# preamp.net
KiCad netlist of a schematic drawn in EAGLE
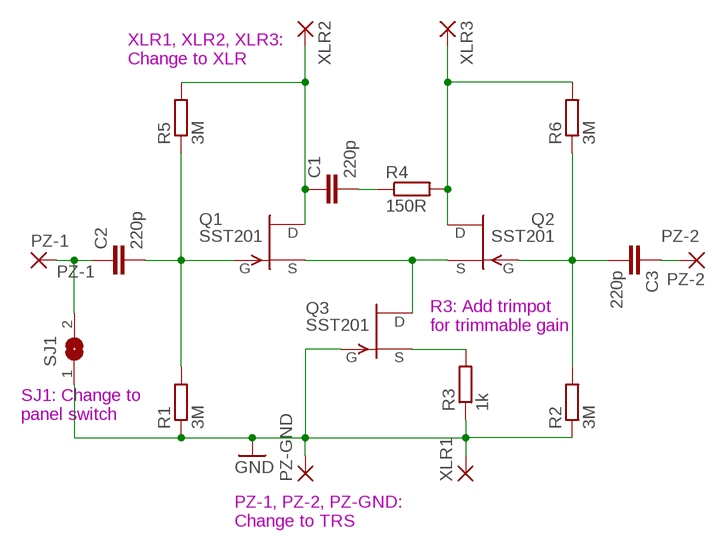
[diagram p0: schematic, sheet 1]

(export (version "E")
  (design (tool "Eeschema 10.0.6"))
  (components
    (comp (ref "C1")
      (value "220p")
      (footprint "eagle-import:C1206")
      (libsource (lib "eagle-import") (part "C-EUC1206"))
    )
    (comp (ref "C2")
      (value "220p")
      (footprint "eagle-import:C1206")
      (libsource (lib "eagle-import") (part "C-EUC1206"))
    )
    (comp (ref "C3")
      (value "220p")
      (footprint "eagle-import:C1206")
      (libsource (lib "eagle-import") (part "C-EUC1206"))
    )
    (comp (ref "PZ-1")
      (value "3,17/1,3")
      (footprint "eagle-import:3,17_1,3")
      (libsource (lib "eagle-import") (part "3,17/1,3"))
    )
    (comp (ref "PZ-2")
      (value "3,17/1,3")
      (footprint "eagle-import:3,17_1,3")
      (libsource (lib "eagle-import") (part "3,17/1,3"))
    )
    (comp (ref "PZ-GND")
      (value "3,17/1,3")
      (footprint "eagle-import:3,17_1,3")
      (libsource (lib "eagle-import") (part "3,17/1,3"))
    )
    (comp (ref "Q1")
      (value "SST201")
      (footprint "eagle-import:SOT23")
      (libsource (lib "eagle-import") (part "?20SST1"))
    )
    (comp (ref "Q2")
      (value "SST201")
      (footprint "eagle-import:SOT23")
      (libsource (lib "eagle-import") (part "?20SST1"))
    )
    (comp (ref "Q3")
      (value "SST201")
      (footprint "eagle-import:SOT23")
      (libsource (lib "eagle-import") (part "?20SST1"))
    )
    (comp (ref "R1")
      (value "3M")
      (footprint "eagle-import:R1206")
      (libsource (lib "eagle-import") (part "R-EU_R1206"))
    )
    (comp (ref "R2")
      (value "3M")
      (footprint "eagle-import:R1206")
      (libsource (lib "eagle-import") (part "R-EU_R1206"))
    )
    (comp (ref "R3")
      (value "1k")
      (footprint "eagle-import:R1206")
      (libsource (lib "eagle-import") (part "R-EU_R1206"))
    )
    (comp (ref "R4")
      (value "150R")
      (footprint "eagle-import:R1206")
      (libsource (lib "eagle-import") (part "R-EU_R1206"))
    )
    (comp (ref "R5")
      (value "3M")
      (footprint "eagle-import:R1206")
      (libsource (lib "eagle-import") (part "R-EU_R1206"))
    )
    (comp (ref "R6")
      (value "3M")
      (footprint "eagle-import:R1206")
      (libsource (lib "eagle-import") (part "R-EU_R1206"))
    )
    (comp (ref "SJ1") (value "SJ") (footprint "eagle-import:SJ") (libsource (lib "eagle-import") (part "SJ")))
    (comp (ref "XLR1")
      (value "3,17/1,3")
      (footprint "eagle-import:3,17_1,3")
      (libsource (lib "eagle-import") (part "3,17/1,3"))
    )
    (comp (ref "XLR2")
      (value "3,17/1,3")
      (footprint "eagle-import:3,17_1,3")
      (libsource (lib "eagle-import") (part "3,17/1,3"))
    )
    (comp (ref "XLR3")
      (value "3,17/1,3")
      (footprint "eagle-import:3,17_1,3")
      (libsource (lib "eagle-import") (part "3,17/1,3"))
    )
  )
  (nets
    (net (code "1") (name "/PZ-1") (class "Default")
      (node (ref "C2") (pin "1") (pinfunction "1_1") (pintype "passive"))
      (node (ref "PZ-1") (pin "1") (pinfunction "P_1") (pintype "passive"))
      (node (ref "SJ1") (pin "2") (pinfunction "2_2") (pintype "passive"))
    )
    (net (code "2") (name "/PZ-2") (class "Default")
      (node (ref "C3") (pin "1") (pinfunction "1_1") (pintype "passive"))
      (node (ref "PZ-2") (pin "1") (pinfunction "P_1") (pintype "passive"))
    )
    (net (code "3") (name "GND") (class "Default")
      (node (ref "PZ-GND") (pin "1") (pinfunction "P_1") (pintype "passive"))
      (node (ref "Q3") (pin "3") (pinfunction "G_3") (pintype "passive"))
      (node (ref "R1") (pin "1") (pinfunction "1_1") (pintype "passive"))
      (node (ref "R2") (pin "1") (pinfunction "1_1") (pintype "passive"))
      (node (ref "R3") (pin "1") (pinfunction "1_1") (pintype "passive"))
      (node (ref "SJ1") (pin "1") (pinfunction "1_1") (pintype "passive"))
      (node (ref "XLR1") (pin "1") (pinfunction "P_1") (pintype "passive"))
    )
    (net (code "4") (name "Net-(C1-Pad2)") (class "Default")
      (node (ref "C1") (pin "2") (pinfunction "2_2") (pintype "passive"))
      (node (ref "R4") (pin "1") (pinfunction "1_1") (pintype "passive"))
    )
    (net (code "5") (name "Net-(Q1-D)") (class "Default")
      (node (ref "C1") (pin "1") (pinfunction "1_1") (pintype "passive"))
      (node (ref "Q1") (pin "1") (pinfunction "D_1") (pintype "passive"))
      (node (ref "R5") (pin "2") (pinfunction "2_2") (pintype "passive"))
      (node (ref "XLR2") (pin "1") (pinfunction "P_1") (pintype "passive"))
    )
    (net (code "6") (name "Net-(Q1-G)") (class "Default")
      (node (ref "C2") (pin "2") (pinfunction "2_2") (pintype "passive"))
      (node (ref "Q1") (pin "3") (pinfunction "G_3") (pintype "passive"))
      (node (ref "R1") (pin "2") (pinfunction "2_2") (pintype "passive"))
      (node (ref "R5") (pin "1") (pinfunction "1_1") (pintype "passive"))
    )
    (net (code "7") (name "Net-(Q1-S)") (class "Default")
      (node (ref "Q1") (pin "2") (pinfunction "S_2") (pintype "passive"))
      (node (ref "Q2") (pin "2") (pinfunction "S_2") (pintype "passive"))
      (node (ref "Q3") (pin "1") (pinfunction "D_1") (pintype "passive"))
    )
    (net (code "8") (name "Net-(Q2-D)") (class "Default")
      (node (ref "Q2") (pin "1") (pinfunction "D_1") (pintype "passive"))
      (node (ref "R4") (pin "2") (pinfunction "2_2") (pintype "passive"))
      (node (ref "R6") (pin "2") (pinfunction "2_2") (pintype "passive"))
      (node (ref "XLR3") (pin "1") (pinfunction "P_1") (pintype "passive"))
    )
    (net (code "9") (name "Net-(Q2-G)") (class "Default")
      (node (ref "C3") (pin "2") (pinfunction "2_2") (pintype "passive"))
      (node (ref "Q2") (pin "3") (pinfunction "G_3") (pintype "passive"))
      (node (ref "R2") (pin "2") (pinfunction "2_2") (pintype "passive"))
      (node (ref "R6") (pin "1") (pinfunction "1_1") (pintype "passive"))
    )
    (net (code "10") (name "Net-(Q3-S)") (class "Default")
      (node (ref "Q3") (pin "2") (pinfunction "S_2") (pintype "passive"))
      (node (ref "R3") (pin "2") (pinfunction "2_2") (pintype "passive"))
    )
  )
)
